# external_fan_controller.net
KiCad netlist of a schematic drawn in EAGLE
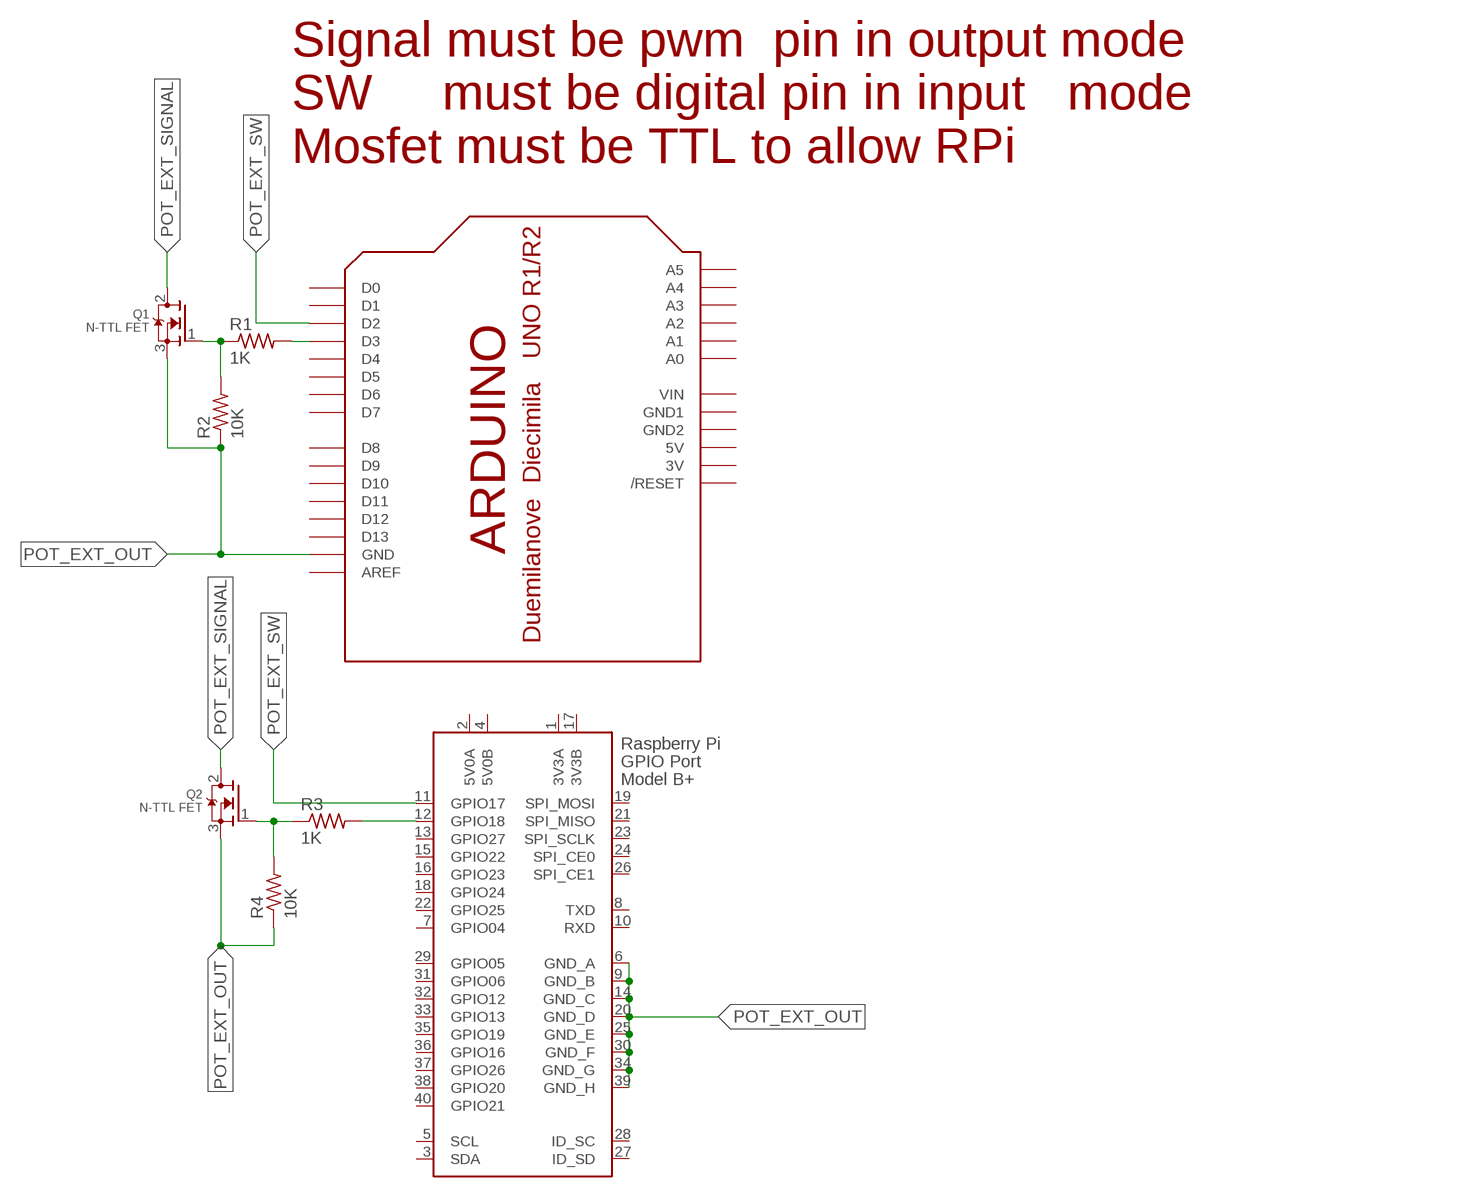
[diagram p0: schematic, sheet 1]

(export (version "E")
  (design (tool "Eeschema 10.0.6"))
  (components
    (comp (ref "Q1")
      (value "N-TTL FET")
      (footprint "eagle-import:TO220V")
      (libsource (lib "eagle-import") (part "MOSFET-NGDS_TO220V"))
    )
    (comp (ref "Q2")
      (value "N-TTL FET")
      (footprint "eagle-import:TO220V")
      (libsource (lib "eagle-import") (part "MOSFET-NGDS_TO220V"))
    )
    (comp (ref "R1")
      (value "1K")
      (footprint "eagle-import:0204_5")
      (libsource (lib "eagle-import") (part "R-US_0204/5"))
    )
    (comp (ref "R2")
      (value "10K")
      (footprint "eagle-import:0204_5")
      (libsource (lib "eagle-import") (part "R-US_0204/5"))
    )
    (comp (ref "R3")
      (value "1K")
      (footprint "eagle-import:0204_5")
      (libsource (lib "eagle-import") (part "R-US_0204/5"))
    )
    (comp (ref "R4")
      (value "10K")
      (footprint "eagle-import:0204_5")
      (libsource (lib "eagle-import") (part "R-US_0204/5"))
    )
    (comp (ref "U$1")
      (value "ARDUINOUNO")
      (footprint "eagle-import:ARDUINO")
      (libsource (lib "eagle-import") (part "ARDUINOUNO"))
    )
    (comp (ref "X1")
      (value "RASPI_BOARD_B+#_HD")
      (footprint "eagle-import:RASPI_BOARD_B+HAT_DF")
      (libsource (lib "eagle-import") (part "RASPI_BOARD_B+#_HD"))
    )
  )
  (nets
    (net (code "1") (name "/3V") (class "Default")
      (node (ref "U$1") (pin "3V") (pinfunction "3V_3V") (pintype "power_in"))
    )
    (net (code "2") (name "/3V3A") (class "Default")
      (node (ref "X1") (pin "1") (pinfunction "3V3A_1") (pintype "power_in"))
    )
    (net (code "3") (name "/3V3B") (class "Default")
      (node (ref "X1") (pin "17") (pinfunction "3V3B_17") (pintype "power_in"))
    )
    (net (code "4") (name "/5V") (class "Default")
      (node (ref "U$1") (pin "5V") (pinfunction "5V_5V") (pintype "power_in"))
    )
    (net (code "5") (name "/5V0A") (class "Default")
      (node (ref "X1") (pin "2") (pinfunction "5V0A_2") (pintype "power_in"))
    )
    (net (code "6") (name "/5V0B") (class "Default")
      (node (ref "X1") (pin "4") (pinfunction "5V0B_4") (pintype "power_in"))
    )
    (net (code "7") (name "/GND1") (class "Default")
      (node (ref "U$1") (pin "GND1") (pinfunction "GND1_GND1") (pintype "power_in"))
    )
    (net (code "8") (name "/GND2") (class "Default")
      (node (ref "U$1") (pin "GND2") (pinfunction "GND2_GND2") (pintype "power_in"))
    )
    (net (code "9") (name "/VIN") (class "Default")
      (node (ref "U$1") (pin "VIN") (pinfunction "VIN_VIN") (pintype "power_in"))
    )
    (net (code "10") (name "Net-(Q1-G)") (class "Default")
      (node (ref "Q1") (pin "1") (pinfunction "G_1") (pintype "bidirectional"))
      (node (ref "R1") (pin "1") (pinfunction "1_1") (pintype "passive"))
      (node (ref "R2") (pin "2") (pinfunction "2_2") (pintype "passive"))
    )
    (net (code "11") (name "Net-(Q2-G)") (class "Default")
      (node (ref "Q2") (pin "1") (pinfunction "G_1") (pintype "bidirectional"))
      (node (ref "R3") (pin "1") (pinfunction "1_1") (pintype "passive"))
      (node (ref "R4") (pin "2") (pinfunction "2_2") (pintype "passive"))
    )
    (net (code "12") (name "Net-(R1-Pad2)") (class "Default")
      (node (ref "R1") (pin "2") (pinfunction "2_2") (pintype "passive"))
      (node (ref "U$1") (pin "D3") (pinfunction "D3_D3") (pintype "bidirectional"))
    )
    (net (code "13") (name "Net-(X1-GPIO18)") (class "Default")
      (node (ref "R3") (pin "2") (pinfunction "2_2") (pintype "passive"))
      (node (ref "X1") (pin "12") (pinfunction "GPIO18_12") (pintype "bidirectional"))
    )
    (net (code "14") (name "POT_EXT_OUT") (class "Default")
      (node (ref "Q1") (pin "3") (pinfunction "S_3") (pintype "bidirectional"))
      (node (ref "Q2") (pin "3") (pinfunction "S_3") (pintype "bidirectional"))
      (node (ref "R2") (pin "1") (pinfunction "1_1") (pintype "passive"))
      (node (ref "R4") (pin "1") (pinfunction "1_1") (pintype "passive"))
      (node (ref "U$1") (pin "GND") (pinfunction "GND_GND") (pintype "power_in"))
      (node (ref "X1") (pin "14") (pinfunction "GND_C_14") (pintype "power_in"))
      (node (ref "X1") (pin "20") (pinfunction "GND_D_20") (pintype "power_in"))
      (node (ref "X1") (pin "25") (pinfunction "GND_E_25") (pintype "power_in"))
      (node (ref "X1") (pin "30") (pinfunction "GND_F_30") (pintype "power_in"))
      (node (ref "X1") (pin "34") (pinfunction "GND_G_34") (pintype "power_in"))
      (node (ref "X1") (pin "39") (pinfunction "GND_H_39") (pintype "power_in"))
      (node (ref "X1") (pin "6") (pinfunction "GND_A_6") (pintype "power_in"))
      (node (ref "X1") (pin "9") (pinfunction "GND_B_9") (pintype "power_in"))
    )
    (net (code "15") (name "POT_EXT_SIGNAL") (class "Default")
      (node (ref "Q1") (pin "2") (pinfunction "D_2") (pintype "bidirectional"))
      (node (ref "Q2") (pin "2") (pinfunction "D_2") (pintype "bidirectional"))
    )
    (net (code "16") (name "POT_EXT_SW") (class "Default")
      (node (ref "U$1") (pin "D2") (pinfunction "D2_D2") (pintype "bidirectional"))
      (node (ref "X1") (pin "11") (pinfunction "GPIO17_11") (pintype "bidirectional"))
    )
    (net (code "17") (name "unconnected-(U$1-PadA0)") (class "Default")
      (node (ref "U$1") (pin "A0") (pinfunction "A0_A0") (pintype "bidirectional"))
    )
    (net (code "18") (name "unconnected-(U$1-PadA1)") (class "Default")
      (node (ref "U$1") (pin "A1") (pinfunction "A1_A1") (pintype "bidirectional"))
    )
    (net (code "19") (name "unconnected-(U$1-PadA2)") (class "Default")
      (node (ref "U$1") (pin "A2") (pinfunction "A2_A2") (pintype "bidirectional"))
    )
    (net (code "20") (name "unconnected-(U$1-PadA3)") (class "Default")
      (node (ref "U$1") (pin "A3") (pinfunction "A3_A3") (pintype "bidirectional"))
    )
    (net (code "21") (name "unconnected-(U$1-PadA4)") (class "Default")
      (node (ref "U$1") (pin "A4") (pinfunction "A4_A4") (pintype "bidirectional"))
    )
    (net (code "22") (name "unconnected-(U$1-PadA5)") (class "Default")
      (node (ref "U$1") (pin "A5") (pinfunction "A5_A5") (pintype "bidirectional"))
    )
    (net (code "23") (name "unconnected-(U$1-PadAREF)") (class "Default")
      (node (ref "U$1") (pin "AREF") (pinfunction "AREF_AREF") (pintype "bidirectional"))
    )
    (net (code "24") (name "unconnected-(U$1-PadD0)") (class "Default")
      (node (ref "U$1") (pin "D0") (pinfunction "D0_D0") (pintype "bidirectional"))
    )
    (net (code "25") (name "unconnected-(U$1-PadD1)") (class "Default")
      (node (ref "U$1") (pin "D1") (pinfunction "D1_D1") (pintype "bidirectional"))
    )
    (net (code "26") (name "unconnected-(U$1-PadD4)") (class "Default")
      (node (ref "U$1") (pin "D4") (pinfunction "D4_D4") (pintype "bidirectional"))
    )
    (net (code "27") (name "unconnected-(U$1-PadD5)") (class "Default")
      (node (ref "U$1") (pin "D5") (pinfunction "D5_D5") (pintype "bidirectional"))
    )
    (net (code "28") (name "unconnected-(U$1-PadD6)") (class "Default")
      (node (ref "U$1") (pin "D6") (pinfunction "D6_D6") (pintype "bidirectional"))
    )
    (net (code "29") (name "unconnected-(U$1-PadD7)") (class "Default")
      (node (ref "U$1") (pin "D7") (pinfunction "D7_D7") (pintype "bidirectional"))
    )
    (net (code "30") (name "unconnected-(U$1-PadD8)") (class "Default")
      (node (ref "U$1") (pin "D8") (pinfunction "D8_D8") (pintype "bidirectional"))
    )
    (net (code "31") (name "unconnected-(U$1-PadD9)") (class "Default")
      (node (ref "U$1") (pin "D9") (pinfunction "D9_D9") (pintype "bidirectional"))
    )
    (net (code "32") (name "unconnected-(U$1-PadD10)") (class "Default")
      (node (ref "U$1") (pin "D10") (pinfunction "D10_D10") (pintype "bidirectional"))
    )
    (net (code "33") (name "unconnected-(U$1-PadD11)") (class "Default")
      (node (ref "U$1") (pin "D11") (pinfunction "D11_D11") (pintype "bidirectional"))
    )
    (net (code "34") (name "unconnected-(U$1-PadD12)") (class "Default")
      (node (ref "U$1") (pin "D12") (pinfunction "D12_D12") (pintype "bidirectional"))
    )
    (net (code "35") (name "unconnected-(U$1-PadD13)") (class "Default")
      (node (ref "U$1") (pin "D13") (pinfunction "D13_D13") (pintype "bidirectional"))
    )
    (net (code "36") (name "unconnected-(U$1-{slash}RESET-PadRESET)") (class "Default")
      (node (ref "U$1") (pin "RESET") (pinfunction "/RESET_RESET") (pintype "bidirectional"))
    )
    (net (code "37") (name "unconnected-(X1-GPIO04-Pad7)") (class "Default")
      (node (ref "X1") (pin "7") (pinfunction "GPIO04_7") (pintype "bidirectional"))
    )
    (net (code "38") (name "unconnected-(X1-GPIO05-Pad29)") (class "Default")
      (node (ref "X1") (pin "29") (pinfunction "GPIO05_29") (pintype "no_connect"))
    )
    (net (code "39") (name "unconnected-(X1-GPIO06-Pad31)") (class "Default")
      (node (ref "X1") (pin "31") (pinfunction "GPIO06_31") (pintype "no_connect"))
    )
    (net (code "40") (name "unconnected-(X1-GPIO12-Pad32)") (class "Default")
      (node (ref "X1") (pin "32") (pinfunction "GPIO12_32") (pintype "no_connect"))
    )
    (net (code "41") (name "unconnected-(X1-GPIO13-Pad33)") (class "Default")
      (node (ref "X1") (pin "33") (pinfunction "GPIO13_33") (pintype "no_connect"))
    )
    (net (code "42") (name "unconnected-(X1-GPIO16-Pad36)") (class "Default")
      (node (ref "X1") (pin "36") (pinfunction "GPIO16_36") (pintype "no_connect"))
    )
    (net (code "43") (name "unconnected-(X1-GPIO19-Pad35)") (class "Default")
      (node (ref "X1") (pin "35") (pinfunction "GPIO19_35") (pintype "no_connect"))
    )
    (net (code "44") (name "unconnected-(X1-GPIO20-Pad38)") (class "Default")
      (node (ref "X1") (pin "38") (pinfunction "GPIO20_38") (pintype "no_connect"))
    )
    (net (code "45") (name "unconnected-(X1-GPIO21-Pad40)") (class "Default")
      (node (ref "X1") (pin "40") (pinfunction "GPIO21_40") (pintype "no_connect"))
    )
    (net (code "46") (name "unconnected-(X1-GPIO22-Pad15)") (class "Default")
      (node (ref "X1") (pin "15") (pinfunction "GPIO22_15") (pintype "bidirectional"))
    )
    (net (code "47") (name "unconnected-(X1-GPIO23-Pad16)") (class "Default")
      (node (ref "X1") (pin "16") (pinfunction "GPIO23_16") (pintype "bidirectional"))
    )
    (net (code "48") (name "unconnected-(X1-GPIO24-Pad18)") (class "Default")
      (node (ref "X1") (pin "18") (pinfunction "GPIO24_18") (pintype "bidirectional"))
    )
    (net (code "49") (name "unconnected-(X1-GPIO25-Pad22)") (class "Default")
      (node (ref "X1") (pin "22") (pinfunction "GPIO25_22") (pintype "bidirectional"))
    )
    (net (code "50") (name "unconnected-(X1-GPIO26-Pad37)") (class "Default")
      (node (ref "X1") (pin "37") (pinfunction "GPIO26_37") (pintype "no_connect"))
    )
    (net (code "51") (name "unconnected-(X1-GPIO27-Pad13)") (class "Default")
      (node (ref "X1") (pin "13") (pinfunction "GPIO27_13") (pintype "bidirectional"))
    )
    (net (code "52") (name "unconnected-(X1-ID_SC-Pad28)") (class "Default")
      (node (ref "X1") (pin "28") (pinfunction "ID_SC_28") (pintype "no_connect"))
    )
    (net (code "53") (name "unconnected-(X1-ID_SD-Pad27)") (class "Default")
      (node (ref "X1") (pin "27") (pinfunction "ID_SD_27") (pintype "no_connect"))
    )
    (net (code "54") (name "unconnected-(X1-RXD-Pad10)") (class "Default")
      (node (ref "X1") (pin "10") (pinfunction "RXD_10") (pintype "bidirectional"))
    )
    (net (code "55") (name "unconnected-(X1-SCL-Pad5)") (class "Default")
      (node (ref "X1") (pin "5") (pinfunction "SCL_5") (pintype "bidirectional"))
    )
    (net (code "56") (name "unconnected-(X1-SDA-Pad3)") (class "Default")
      (node (ref "X1") (pin "3") (pinfunction "SDA_3") (pintype "bidirectional"))
    )
    (net (code "57") (name "unconnected-(X1-SPI_CE0-Pad24)") (class "Default")
      (node (ref "X1") (pin "24") (pinfunction "SPI_CE0_24") (pintype "bidirectional"))
    )
    (net (code "58") (name "unconnected-(X1-SPI_CE1-Pad26)") (class "Default")
      (node (ref "X1") (pin "26") (pinfunction "SPI_CE1_26") (pintype "bidirectional"))
    )
    (net (code "59") (name "unconnected-(X1-SPI_MISO-Pad21)") (class "Default")
      (node (ref "X1") (pin "21") (pinfunction "SPI_MISO_21") (pintype "bidirectional"))
    )
    (net (code "60") (name "unconnected-(X1-SPI_MOSI-Pad19)") (class "Default")
      (node (ref "X1") (pin "19") (pinfunction "SPI_MOSI_19") (pintype "bidirectional"))
    )
    (net (code "61") (name "unconnected-(X1-SPI_SCLK-Pad23)") (class "Default")
      (node (ref "X1") (pin "23") (pinfunction "SPI_SCLK_23") (pintype "bidirectional"))
    )
    (net (code "62") (name "unconnected-(X1-TXD-Pad8)") (class "Default")
      (node (ref "X1") (pin "8") (pinfunction "TXD_8") (pintype "bidirectional"))
    )
  )
)
